# LoRaMicrobit1_0.net
KiCad netlist of a schematic drawn in EAGLE
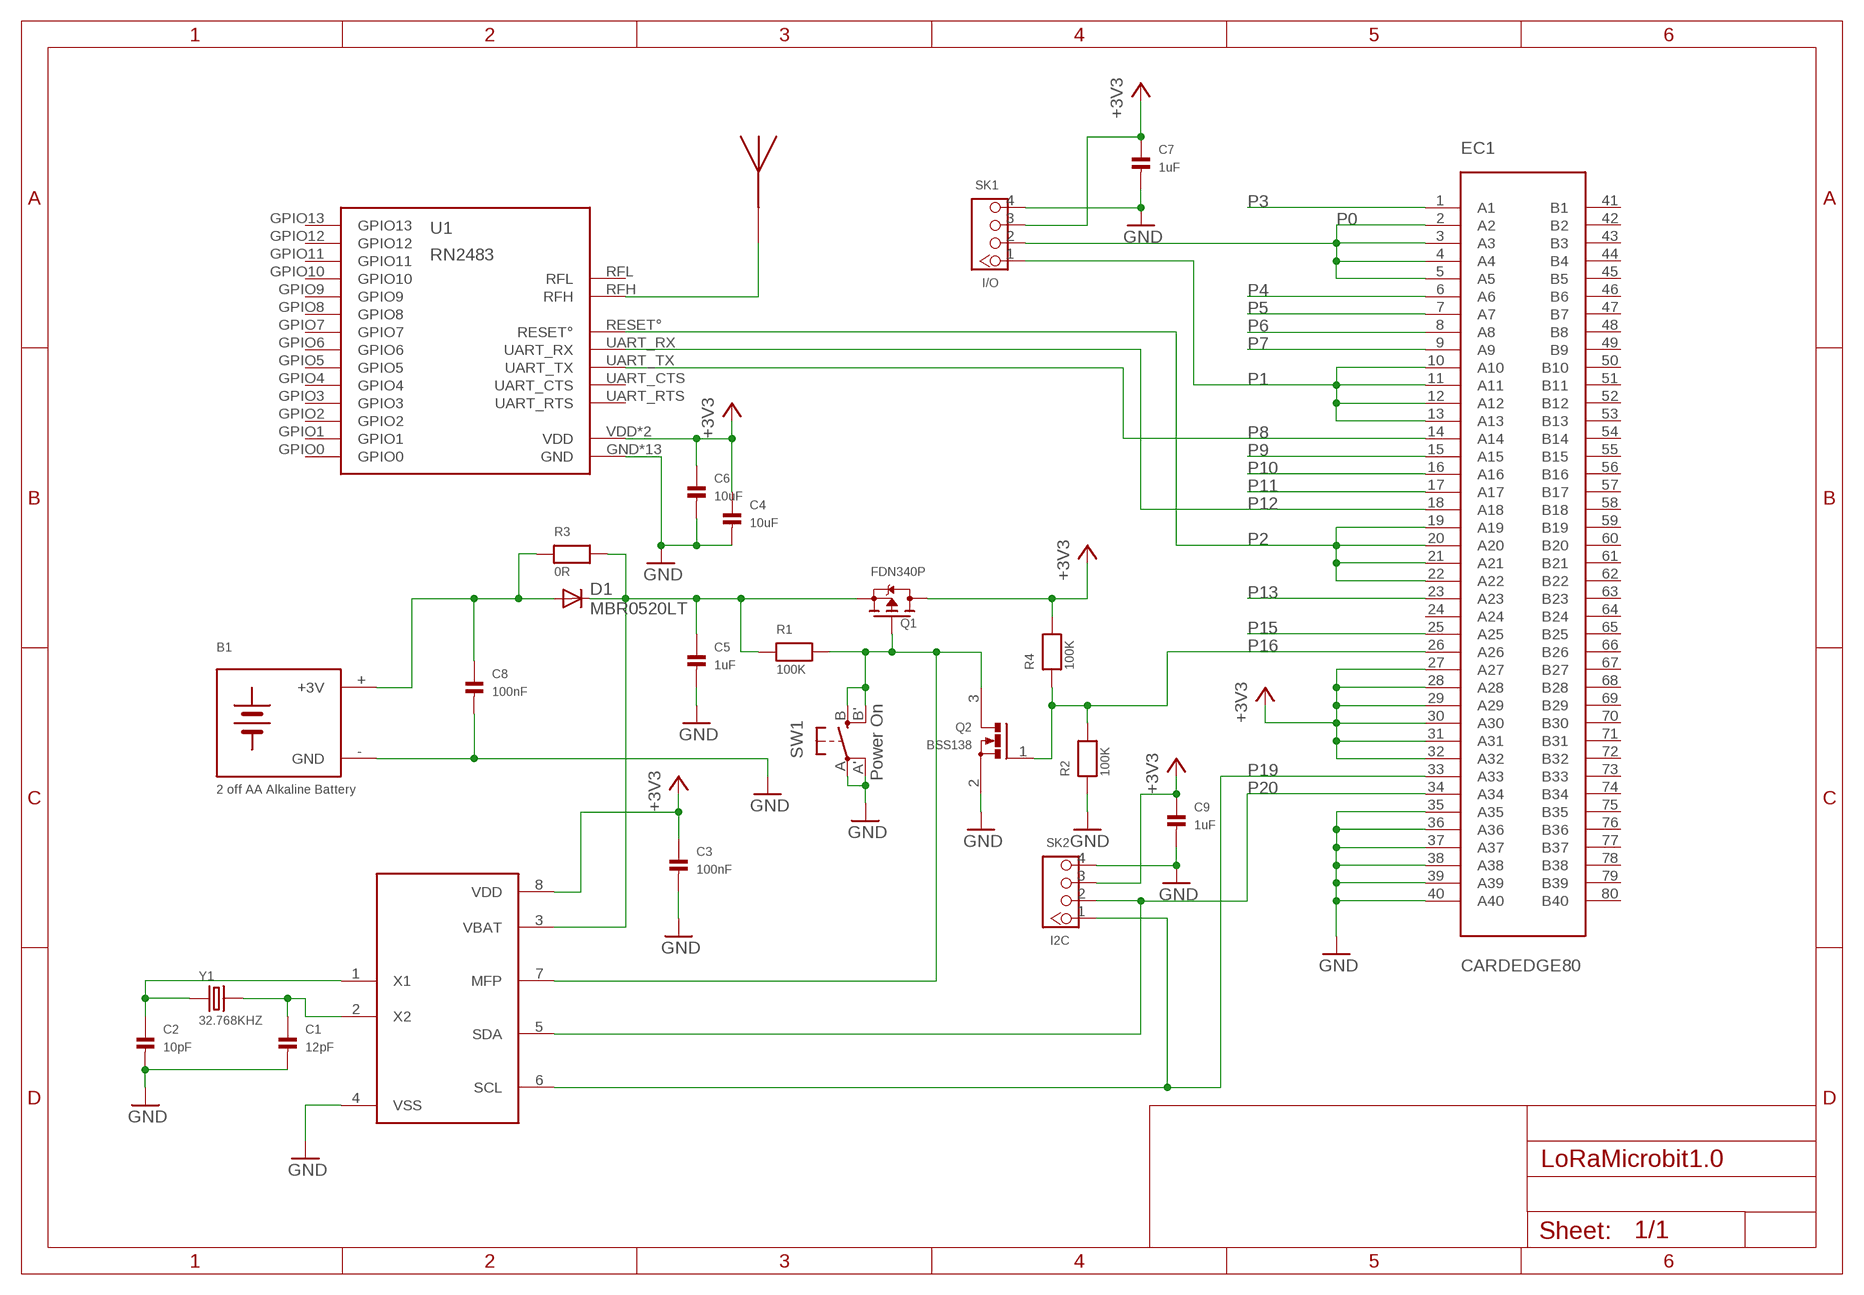
[diagram p0: schematic, sheet 1]

(export (version "E")
  (design (tool "Eeschema 10.0.6"))
  (components
    (comp (ref "B1")
      (value "2 off AA Alkaline Battery")
      (footprint "eagle-import:2AABATTERY")
      (libsource (lib "eagle-import") (part "2AABATTERY"))
    )
    (comp (ref "C1")
      (value "12pF")
      (footprint "eagle-import:0603")
      (libsource (lib "eagle-import") (part "CAP_CERAMIC0603"))
    )
    (comp (ref "C2")
      (value "10pF")
      (footprint "eagle-import:0603")
      (libsource (lib "eagle-import") (part "CAP_CERAMIC0603"))
    )
    (comp (ref "C3")
      (value "100nF")
      (footprint "eagle-import:0603")
      (libsource (lib "eagle-import") (part "CAP_CERAMIC0603"))
    )
    (comp (ref "C4")
      (value "10uF")
      (footprint "eagle-import:0603")
      (libsource (lib "eagle-import") (part "CAP_CERAMIC0603"))
    )
    (comp (ref "C5")
      (value "1uF")
      (footprint "eagle-import:0603")
      (libsource (lib "eagle-import") (part "CAP_CERAMIC0603"))
    )
    (comp (ref "C6")
      (value "10uF")
      (footprint "eagle-import:0603")
      (libsource (lib "eagle-import") (part "CAP_CERAMIC0603"))
    )
    (comp (ref "C7")
      (value "1uF")
      (footprint "eagle-import:0603")
      (libsource (lib "eagle-import") (part "CAP_CERAMIC0603"))
    )
    (comp (ref "C8")
      (value "100nF")
      (footprint "eagle-import:0603")
      (libsource (lib "eagle-import") (part "CAP_CERAMIC0603"))
    )
    (comp (ref "C9")
      (value "1uF")
      (footprint "eagle-import:0603")
      (libsource (lib "eagle-import") (part "CAP_CERAMIC0603"))
    )
    (comp (ref "D1")
      (value "MBR0520LT")
      (footprint "eagle-import:SOD123")
      (libsource (lib "eagle-import") (part "MBR0520LT"))
    )
    (comp (ref "EC1")
      (value "CARDEDGE80")
      (footprint "eagle-import:CARDEDGE80")
      (libsource (lib "eagle-import") (part "CARDEDGE80"))
    )
    (comp (ref "Q1")
      (value "FDN340P")
      (footprint "eagle-import:SOT23-R")
      (libsource (lib "eagle-import") (part "MOSFET-P"))
    )
    (comp (ref "Q2")
      (value "BSS138")
      (footprint "eagle-import:SOT23-R")
      (libsource (lib "eagle-import") (part "MOSFET-NREFLOW"))
    )
    (comp (ref "R1")
      (value "100K")
      (footprint "eagle-import:0603")
      (libsource (lib "eagle-import") (part "RESISTOR0603"))
    )
    (comp (ref "R2")
      (value "100K")
      (footprint "eagle-import:0603")
      (libsource (lib "eagle-import") (part "RESISTOR0603"))
    )
    (comp (ref "R3")
      (value "0R")
      (footprint "eagle-import:0603")
      (libsource (lib "eagle-import") (part "RESISTOR0603"))
    )
    (comp (ref "R4")
      (value "100K")
      (footprint "eagle-import:0603")
      (libsource (lib "eagle-import") (part "RESISTOR0603"))
    )
    (comp (ref "SK1")
      (value "I/O")
      (footprint "eagle-import:HW4-2.0-90D")
      (libsource (lib "eagle-import") (part "GROVE-CONNECTOR-DIP-90D(4P-2.0)"))
    )
    (comp (ref "SK2")
      (value "I2C")
      (footprint "eagle-import:HW4-2.0-90D")
      (libsource (lib "eagle-import") (part "GROVE-CONNECTOR-DIP-90D(4P-2.0)"))
    )
    (comp (ref "SW1")
      (value "Power On")
      (footprint "eagle-import:EVQ-Q2")
      (libsource (lib "eagle-import") (part "SPST_TACT-EVQQ2"))
    )
    (comp (ref "U$2")
      (value "0868AT43A0020")
      (footprint "eagle-import:0868AT043A0020")
      (libsource (lib "eagle-import") (part "0868AT43A0020"))
    )
    (comp (ref "U1")
      (value "RN2483")
      (footprint "eagle-import:RN2483")
      (libsource (lib "eagle-import") (part "RN2483"))
    )
    (comp (ref "U2")
      (value "MCP7940N")
      (footprint "eagle-import:SOIC8-N_MC")
      (libsource (lib "eagle-import") (part "MCP7940N"))
    )
    (comp (ref "Y1")
      (value "32.768KHZ")
      (footprint "eagle-import:X2-SMD-3.2X1.5X0.55MM")
      (fields (field (name "MPN") "FC-135"))
      (libsource (lib "eagle-import") (part "SMD-CRYSTAL-ABS07-32.768KHZ-7PF-20PPM-70K(2P-3.2X1.5MM)"))
    )
  )
  (nets
    (net (code "1") (name "+3V3") (class "Default")
      (node (ref "C3") (pin "1") (pinfunction "P$1_1") (pintype "passive"))
      (node (ref "C4") (pin "1") (pinfunction "P$1_1") (pintype "passive"))
      (node (ref "C6") (pin "1") (pinfunction "P$1_1") (pintype "passive"))
      (node (ref "C7") (pin "1") (pinfunction "P$1_1") (pintype "passive"))
      (node (ref "C9") (pin "1") (pinfunction "P$1_1") (pintype "passive"))
      (node (ref "EC1") (pin "27") (pinfunction "A27_27") (pintype "bidirectional"))
      (node (ref "EC1") (pin "28") (pinfunction "A28_28") (pintype "bidirectional"))
      (node (ref "EC1") (pin "29") (pinfunction "A29_29") (pintype "bidirectional"))
      (node (ref "EC1") (pin "30") (pinfunction "A30_30") (pintype "bidirectional"))
      (node (ref "EC1") (pin "31") (pinfunction "A31_31") (pintype "bidirectional"))
      (node (ref "EC1") (pin "32") (pinfunction "A32_32") (pintype "bidirectional"))
      (node (ref "Q1") (pin "3") (pinfunction "D_3") (pintype "passive"))
      (node (ref "R4") (pin "2") (pinfunction "2_2") (pintype "passive"))
      (node (ref "SK1") (pin "3") (pinfunction "3_3") (pintype "bidirectional"))
      (node (ref "SK2") (pin "3") (pinfunction "3_3") (pintype "bidirectional"))
      (node (ref "U1") (pin "VDD") (pinfunction "VDD_VDD") (pintype "bidirectional"))
      (node (ref "U1") (pin "VDD2") (pinfunction "VDD_VDD2") (pintype "bidirectional"))
      (node (ref "U2") (pin "8") (pinfunction "VDD_8") (pintype "power_in"))
    )
    (net (code "2") (name "/P0") (class "Default")
      (node (ref "EC1") (pin "2") (pinfunction "A2_2") (pintype "bidirectional"))
      (node (ref "EC1") (pin "3") (pinfunction "A3_3") (pintype "bidirectional"))
      (node (ref "EC1") (pin "4") (pinfunction "A4_4") (pintype "bidirectional"))
      (node (ref "EC1") (pin "5") (pinfunction "A5_5") (pintype "bidirectional"))
      (node (ref "SK1") (pin "2") (pinfunction "2_2") (pintype "bidirectional"))
    )
    (net (code "3") (name "/P1") (class "Default")
      (node (ref "EC1") (pin "10") (pinfunction "A10_10") (pintype "bidirectional"))
      (node (ref "EC1") (pin "11") (pinfunction "A11_11") (pintype "bidirectional"))
      (node (ref "EC1") (pin "12") (pinfunction "A12_12") (pintype "bidirectional"))
      (node (ref "EC1") (pin "13") (pinfunction "A13_13") (pintype "bidirectional"))
      (node (ref "SK1") (pin "1") (pinfunction "1_1") (pintype "bidirectional"))
    )
    (net (code "4") (name "/P2") (class "Default")
      (node (ref "EC1") (pin "19") (pinfunction "A19_19") (pintype "bidirectional"))
      (node (ref "EC1") (pin "20") (pinfunction "A20_20") (pintype "bidirectional"))
      (node (ref "EC1") (pin "21") (pinfunction "A21_21") (pintype "bidirectional"))
      (node (ref "EC1") (pin "22") (pinfunction "A22_22") (pintype "bidirectional"))
      (node (ref "U1") (pin "RESET°") (pinfunction "RESET°_RESET°") (pintype "bidirectional"))
    )
    (net (code "5") (name "/P3") (class "Default")
      (node (ref "EC1") (pin "1") (pinfunction "A1_1") (pintype "bidirectional"))
    )
    (net (code "6") (name "/P4") (class "Default")
      (node (ref "EC1") (pin "6") (pinfunction "A6_6") (pintype "bidirectional"))
    )
    (net (code "7") (name "/P5") (class "Default")
      (node (ref "EC1") (pin "7") (pinfunction "A7_7") (pintype "bidirectional"))
    )
    (net (code "8") (name "/P6") (class "Default")
      (node (ref "EC1") (pin "8") (pinfunction "A8_8") (pintype "bidirectional"))
    )
    (net (code "9") (name "/P7") (class "Default")
      (node (ref "EC1") (pin "9") (pinfunction "A9_9") (pintype "bidirectional"))
    )
    (net (code "10") (name "/P8") (class "Default")
      (node (ref "EC1") (pin "14") (pinfunction "A14_14") (pintype "bidirectional"))
      (node (ref "U1") (pin "UART_TX") (pinfunction "UART_TX_UART_TX") (pintype "bidirectional"))
    )
    (net (code "11") (name "/P9") (class "Default")
      (node (ref "EC1") (pin "15") (pinfunction "A15_15") (pintype "bidirectional"))
    )
    (net (code "12") (name "/P10") (class "Default")
      (node (ref "EC1") (pin "16") (pinfunction "A16_16") (pintype "bidirectional"))
    )
    (net (code "13") (name "/P11") (class "Default")
      (node (ref "EC1") (pin "17") (pinfunction "A17_17") (pintype "bidirectional"))
    )
    (net (code "14") (name "/P12") (class "Default")
      (node (ref "EC1") (pin "18") (pinfunction "A18_18") (pintype "bidirectional"))
      (node (ref "U1") (pin "UART_RX") (pinfunction "UART_RX_UART_RX") (pintype "bidirectional"))
    )
    (net (code "15") (name "/P13") (class "Default")
      (node (ref "EC1") (pin "23") (pinfunction "A23_23") (pintype "bidirectional"))
    )
    (net (code "16") (name "/P15") (class "Default")
      (node (ref "EC1") (pin "25") (pinfunction "A25_25") (pintype "bidirectional"))
    )
    (net (code "17") (name "/P16") (class "Default")
      (node (ref "EC1") (pin "26") (pinfunction "A26_26") (pintype "bidirectional"))
      (node (ref "Q2") (pin "1") (pinfunction "G_1") (pintype "bidirectional"))
      (node (ref "R2") (pin "2") (pinfunction "2_2") (pintype "passive"))
      (node (ref "R4") (pin "1") (pinfunction "1_1") (pintype "passive"))
    )
    (net (code "18") (name "/P19") (class "Default")
      (node (ref "EC1") (pin "33") (pinfunction "A33_33") (pintype "bidirectional"))
      (node (ref "SK2") (pin "1") (pinfunction "1_1") (pintype "bidirectional"))
      (node (ref "U2") (pin "6") (pinfunction "SCL_6") (pintype "bidirectional"))
    )
    (net (code "19") (name "/P20") (class "Default")
      (node (ref "EC1") (pin "34") (pinfunction "A34_34") (pintype "bidirectional"))
      (node (ref "SK2") (pin "2") (pinfunction "2_2") (pintype "bidirectional"))
      (node (ref "U2") (pin "5") (pinfunction "SDA_5") (pintype "bidirectional"))
    )
    (net (code "20") (name "GND") (class "Default")
      (node (ref "B1") (pin "-") (pinfunction "GND_-") (pintype "power_in"))
      (node (ref "C1") (pin "2") (pinfunction "P$2_2") (pintype "passive"))
      (node (ref "C2") (pin "2") (pinfunction "P$2_2") (pintype "passive"))
      (node (ref "C3") (pin "2") (pinfunction "P$2_2") (pintype "passive"))
      (node (ref "C4") (pin "2") (pinfunction "P$2_2") (pintype "passive"))
      (node (ref "C5") (pin "2") (pinfunction "P$2_2") (pintype "passive"))
      (node (ref "C6") (pin "2") (pinfunction "P$2_2") (pintype "passive"))
      (node (ref "C7") (pin "2") (pinfunction "P$2_2") (pintype "passive"))
      (node (ref "C8") (pin "2") (pinfunction "P$2_2") (pintype "passive"))
      (node (ref "C9") (pin "2") (pinfunction "P$2_2") (pintype "passive"))
      (node (ref "EC1") (pin "35") (pinfunction "A35_35") (pintype "bidirectional"))
      (node (ref "EC1") (pin "36") (pinfunction "A36_36") (pintype "bidirectional"))
      (node (ref "EC1") (pin "37") (pinfunction "A37_37") (pintype "bidirectional"))
      (node (ref "EC1") (pin "38") (pinfunction "A38_38") (pintype "bidirectional"))
      (node (ref "EC1") (pin "39") (pinfunction "A39_39") (pintype "bidirectional"))
      (node (ref "EC1") (pin "40") (pinfunction "A40_40") (pintype "bidirectional"))
      (node (ref "Q2") (pin "2") (pinfunction "S_2") (pintype "bidirectional"))
      (node (ref "R2") (pin "1") (pinfunction "1_1") (pintype "passive"))
      (node (ref "SK1") (pin "4") (pinfunction "4_4") (pintype "bidirectional"))
      (node (ref "SK2") (pin "4") (pinfunction "4_4") (pintype "bidirectional"))
      (node (ref "SW1") (pin "A") (pinfunction "P_A") (pintype "passive"))
      (node (ref "SW1") (pin "A'") (pinfunction "P1_A'") (pintype "passive"))
      (node (ref "U1") (pin "GND") (pinfunction "GND_GND") (pintype "bidirectional"))
      (node (ref "U1") (pin "GND1") (pinfunction "GND_GND1") (pintype "bidirectional"))
      (node (ref "U1") (pin "GND10") (pinfunction "GND_GND10") (pintype "bidirectional"))
      (node (ref "U1") (pin "GND11") (pinfunction "GND_GND11") (pintype "bidirectional"))
      (node (ref "U1") (pin "GND12") (pinfunction "GND_GND12") (pintype "bidirectional"))
      (node (ref "U1") (pin "GND2") (pinfunction "GND_GND2") (pintype "bidirectional"))
      (node (ref "U1") (pin "GND3") (pinfunction "GND_GND3") (pintype "bidirectional"))
      (node (ref "U1") (pin "GND4") (pinfunction "GND_GND4") (pintype "bidirectional"))
      (node (ref "U1") (pin "GND5") (pinfunction "GND_GND5") (pintype "bidirectional"))
      (node (ref "U1") (pin "GND6") (pinfunction "GND_GND6") (pintype "bidirectional"))
      (node (ref "U1") (pin "GND7") (pinfunction "GND_GND7") (pintype "bidirectional"))
      (node (ref "U1") (pin "GND8") (pinfunction "GND_GND8") (pintype "bidirectional"))
      (node (ref "U1") (pin "GND9") (pinfunction "GND_GND9") (pintype "bidirectional"))
      (node (ref "U2") (pin "4") (pinfunction "VSS_4") (pintype "power_in"))
    )
    (net (code "21") (name "Net-(B1-+3V)") (class "Default")
      (node (ref "B1") (pin "+") (pinfunction "+3V_+") (pintype "power_in"))
      (node (ref "C8") (pin "1") (pinfunction "P$1_1") (pintype "passive"))
      (node (ref "D1") (pin "A") (pinfunction "A_A") (pintype "passive"))
      (node (ref "R3") (pin "1") (pinfunction "1_1") (pintype "passive"))
    )
    (net (code "22") (name "Net-(C1-P$1)") (class "Default")
      (node (ref "C1") (pin "1") (pinfunction "P$1_1") (pintype "passive"))
      (node (ref "U2") (pin "2") (pinfunction "X2_2") (pintype "bidirectional"))
      (node (ref "Y1") (pin "2") (pinfunction "2_2") (pintype "passive"))
    )
    (net (code "23") (name "Net-(C2-P$1)") (class "Default")
      (node (ref "C2") (pin "1") (pinfunction "P$1_1") (pintype "passive"))
      (node (ref "U2") (pin "1") (pinfunction "X1_1") (pintype "bidirectional"))
      (node (ref "Y1") (pin "1") (pinfunction "1_1") (pintype "passive"))
    )
    (net (code "24") (name "Net-(C5-P$1)") (class "Default")
      (node (ref "C5") (pin "1") (pinfunction "P$1_1") (pintype "passive"))
      (node (ref "D1") (pin "C") (pinfunction "C_C") (pintype "passive"))
      (node (ref "Q1") (pin "2") (pinfunction "S_2") (pintype "passive"))
      (node (ref "R1") (pin "1") (pinfunction "1_1") (pintype "passive"))
      (node (ref "R3") (pin "2") (pinfunction "2_2") (pintype "passive"))
      (node (ref "U2") (pin "3") (pinfunction "VBAT_3") (pintype "power_in"))
    )
    (net (code "25") (name "Net-(Q1-G)") (class "Default")
      (node (ref "Q1") (pin "1") (pinfunction "G_1") (pintype "passive"))
      (node (ref "Q2") (pin "3") (pinfunction "D_3") (pintype "bidirectional"))
      (node (ref "R1") (pin "2") (pinfunction "2_2") (pintype "passive"))
      (node (ref "SW1") (pin "B") (pinfunction "S_B") (pintype "passive"))
      (node (ref "SW1") (pin "B'") (pinfunction "S1_B'") (pintype "passive"))
      (node (ref "U2") (pin "7") (pinfunction "MFP_7") (pintype "output"))
    )
    (net (code "26") (name "Net-(U$2-PadP$1)") (class "Default")
      (node (ref "U$2") (pin "P$1") (pinfunction "P$1_P$1") (pintype "bidirectional"))
      (node (ref "U1") (pin "RFH") (pinfunction "RFH_RFH") (pintype "bidirectional"))
    )
    (net (code "27") (name "unconnected-(EC1-A24-Pad24)") (class "Default")
      (node (ref "EC1") (pin "24") (pinfunction "A24_24") (pintype "bidirectional"))
    )
    (net (code "28") (name "unconnected-(EC1-B1-Pad41)") (class "Default")
      (node (ref "EC1") (pin "41") (pinfunction "B1_41") (pintype "bidirectional"))
    )
    (net (code "29") (name "unconnected-(EC1-B2-Pad42)") (class "Default")
      (node (ref "EC1") (pin "42") (pinfunction "B2_42") (pintype "bidirectional"))
    )
    (net (code "30") (name "unconnected-(EC1-B3-Pad43)") (class "Default")
      (node (ref "EC1") (pin "43") (pinfunction "B3_43") (pintype "bidirectional"))
    )
    (net (code "31") (name "unconnected-(EC1-B4-Pad44)") (class "Default")
      (node (ref "EC1") (pin "44") (pinfunction "B4_44") (pintype "bidirectional"))
    )
    (net (code "32") (name "unconnected-(EC1-B5-Pad45)") (class "Default")
      (node (ref "EC1") (pin "45") (pinfunction "B5_45") (pintype "bidirectional"))
    )
    (net (code "33") (name "unconnected-(EC1-B6-Pad46)") (class "Default")
      (node (ref "EC1") (pin "46") (pinfunction "B6_46") (pintype "bidirectional"))
    )
    (net (code "34") (name "unconnected-(EC1-B7-Pad47)") (class "Default")
      (node (ref "EC1") (pin "47") (pinfunction "B7_47") (pintype "bidirectional"))
    )
    (net (code "35") (name "unconnected-(EC1-B8-Pad48)") (class "Default")
      (node (ref "EC1") (pin "48") (pinfunction "B8_48") (pintype "bidirectional"))
    )
    (net (code "36") (name "unconnected-(EC1-B9-Pad49)") (class "Default")
      (node (ref "EC1") (pin "49") (pinfunction "B9_49") (pintype "bidirectional"))
    )
    (net (code "37") (name "unconnected-(EC1-B10-Pad50)") (class "Default")
      (node (ref "EC1") (pin "50") (pinfunction "B10_50") (pintype "bidirectional"))
    )
    (net (code "38") (name "unconnected-(EC1-B11-Pad51)") (class "Default")
      (node (ref "EC1") (pin "51") (pinfunction "B11_51") (pintype "bidirectional"))
    )
    (net (code "39") (name "unconnected-(EC1-B12-Pad52)") (class "Default")
      (node (ref "EC1") (pin "52") (pinfunction "B12_52") (pintype "bidirectional"))
    )
    (net (code "40") (name "unconnected-(EC1-B13-Pad53)") (class "Default")
      (node (ref "EC1") (pin "53") (pinfunction "B13_53") (pintype "bidirectional"))
    )
    (net (code "41") (name "unconnected-(EC1-B14-Pad54)") (class "Default")
      (node (ref "EC1") (pin "54") (pinfunction "B14_54") (pintype "bidirectional"))
    )
    (net (code "42") (name "unconnected-(EC1-B15-Pad55)") (class "Default")
      (node (ref "EC1") (pin "55") (pinfunction "B15_55") (pintype "bidirectional"))
    )
    (net (code "43") (name "unconnected-(EC1-B16-Pad56)") (class "Default")
      (node (ref "EC1") (pin "56") (pinfunction "B16_56") (pintype "bidirectional"))
    )
    (net (code "44") (name "unconnected-(EC1-B17-Pad57)") (class "Default")
      (node (ref "EC1") (pin "57") (pinfunction "B17_57") (pintype "bidirectional"))
    )
    (net (code "45") (name "unconnected-(EC1-B18-Pad58)") (class "Default")
      (node (ref "EC1") (pin "58") (pinfunction "B18_58") (pintype "bidirectional"))
    )
    (net (code "46") (name "unconnected-(EC1-B19-Pad59)") (class "Default")
      (node (ref "EC1") (pin "59") (pinfunction "B19_59") (pintype "bidirectional"))
    )
    (net (code "47") (name "unconnected-(EC1-B20-Pad60)") (class "Default")
      (node (ref "EC1") (pin "60") (pinfunction "B20_60") (pintype "bidirectional"))
    )
    (net (code "48") (name "unconnected-(EC1-B21-Pad61)") (class "Default")
      (node (ref "EC1") (pin "61") (pinfunction "B21_61") (pintype "bidirectional"))
    )
    (net (code "49") (name "unconnected-(EC1-B22-Pad62)") (class "Default")
      (node (ref "EC1") (pin "62") (pinfunction "B22_62") (pintype "bidirectional"))
    )
    (net (code "50") (name "unconnected-(EC1-B23-Pad63)") (class "Default")
      (node (ref "EC1") (pin "63") (pinfunction "B23_63") (pintype "bidirectional"))
    )
    (net (code "51") (name "unconnected-(EC1-B24-Pad64)") (class "Default")
      (node (ref "EC1") (pin "64") (pinfunction "B24_64") (pintype "bidirectional"))
    )
    (net (code "52") (name "unconnected-(EC1-B25-Pad65)") (class "Default")
      (node (ref "EC1") (pin "65") (pinfunction "B25_65") (pintype "bidirectional"))
    )
    (net (code "53") (name "unconnected-(EC1-B26-Pad66)") (class "Default")
      (node (ref "EC1") (pin "66") (pinfunction "B26_66") (pintype "bidirectional"))
    )
    (net (code "54") (name "unconnected-(EC1-B27-Pad67)") (class "Default")
      (node (ref "EC1") (pin "67") (pinfunction "B27_67") (pintype "bidirectional"))
    )
    (net (code "55") (name "unconnected-(EC1-B28-Pad68)") (class "Default")
      (node (ref "EC1") (pin "68") (pinfunction "B28_68") (pintype "bidirectional"))
    )
    (net (code "56") (name "unconnected-(EC1-B29-Pad69)") (class "Default")
      (node (ref "EC1") (pin "69") (pinfunction "B29_69") (pintype "bidirectional"))
    )
    (net (code "57") (name "unconnected-(EC1-B30-Pad70)") (class "Default")
      (node (ref "EC1") (pin "70") (pinfunction "B30_70") (pintype "bidirectional"))
    )
    (net (code "58") (name "unconnected-(EC1-B31-Pad71)") (class "Default")
      (node (ref "EC1") (pin "71") (pinfunction "B31_71") (pintype "bidirectional"))
    )
    (net (code "59") (name "unconnected-(EC1-B32-Pad72)") (class "Default")
      (node (ref "EC1") (pin "72") (pinfunction "B32_72") (pintype "bidirectional"))
    )
    (net (code "60") (name "unconnected-(EC1-B33-Pad73)") (class "Default")
      (node (ref "EC1") (pin "73") (pinfunction "B33_73") (pintype "bidirectional"))
    )
    (net (code "61") (name "unconnected-(EC1-B34-Pad74)") (class "Default")
      (node (ref "EC1") (pin "74") (pinfunction "B34_74") (pintype "bidirectional"))
    )
    (net (code "62") (name "unconnected-(EC1-B35-Pad75)") (class "Default")
      (node (ref "EC1") (pin "75") (pinfunction "B35_75") (pintype "bidirectional"))
    )
    (net (code "63") (name "unconnected-(EC1-B36-Pad76)") (class "Default")
      (node (ref "EC1") (pin "76") (pinfunction "B36_76") (pintype "bidirectional"))
    )
    (net (code "64") (name "unconnected-(EC1-B37-Pad77)") (class "Default")
      (node (ref "EC1") (pin "77") (pinfunction "B37_77") (pintype "bidirectional"))
    )
    (net (code "65") (name "unconnected-(EC1-B38-Pad78)") (class "Default")
      (node (ref "EC1") (pin "78") (pinfunction "B38_78") (pintype "bidirectional"))
    )
    (net (code "66") (name "unconnected-(EC1-B39-Pad79)") (class "Default")
      (node (ref "EC1") (pin "79") (pinfunction "B39_79") (pintype "bidirectional"))
    )
    (net (code "67") (name "unconnected-(EC1-B40-Pad80)") (class "Default")
      (node (ref "EC1") (pin "80") (pinfunction "B40_80") (pintype "bidirectional"))
    )
    (net (code "68") (name "unconnected-(U1-PadGPIO0)") (class "Default")
      (node (ref "U1") (pin "GPIO0") (pinfunction "GPIO0_GPIO0") (pintype "bidirectional"))
    )
    (net (code "69") (name "unconnected-(U1-PadGPIO1)") (class "Default")
      (node (ref "U1") (pin "GPIO1") (pinfunction "GPIO1_GPIO1") (pintype "bidirectional"))
    )
    (net (code "70") (name "unconnected-(U1-PadGPIO2)") (class "Default")
      (node (ref "U1") (pin "GPIO2") (pinfunction "GPIO2_GPIO2") (pintype "bidirectional"))
    )
    (net (code "71") (name "unconnected-(U1-PadGPIO3)") (class "Default")
      (node (ref "U1") (pin "GPIO3") (pinfunction "GPIO3_GPIO3") (pintype "bidirectional"))
    )
    (net (code "72") (name "unconnected-(U1-PadGPIO4)") (class "Default")
      (node (ref "U1") (pin "GPIO4") (pinfunction "GPIO4_GPIO4") (pintype "bidirectional"))
    )
    (net (code "73") (name "unconnected-(U1-PadGPIO5)") (class "Default")
      (node (ref "U1") (pin "GPIO5") (pinfunction "GPIO5_GPIO5") (pintype "bidirectional"))
    )
    (net (code "74") (name "unconnected-(U1-PadGPIO6)") (class "Default")
      (node (ref "U1") (pin "GPIO6") (pinfunction "GPIO6_GPIO6") (pintype "bidirectional"))
    )
    (net (code "75") (name "unconnected-(U1-PadGPIO7)") (class "Default")
      (node (ref "U1") (pin "GPIO7") (pinfunction "GPIO7_GPIO7") (pintype "bidirectional"))
    )
    (net (code "76") (name "unconnected-(U1-PadGPIO8)") (class "Default")
      (node (ref "U1") (pin "GPIO8") (pinfunction "GPIO8_GPIO8") (pintype "bidirectional"))
    )
    (net (code "77") (name "unconnected-(U1-PadGPIO9)") (class "Default")
      (node (ref "U1") (pin "GPIO9") (pinfunction "GPIO9_GPIO9") (pintype "bidirectional"))
    )
    (net (code "78") (name "unconnected-(U1-PadGPIO10)") (class "Default")
      (node (ref "U1") (pin "GPIO10") (pinfunction "GPIO10_GPIO10") (pintype "bidirectional"))
    )
    (net (code "79") (name "unconnected-(U1-PadGPIO11)") (class "Default")
      (node (ref "U1") (pin "GPIO11") (pinfunction "GPIO11_GPIO11") (pintype "bidirectional"))
    )
    (net (code "80") (name "unconnected-(U1-PadGPIO12)") (class "Default")
      (node (ref "U1") (pin "GPIO12") (pinfunction "GPIO12_GPIO12") (pintype "bidirectional"))
    )
    (net (code "81") (name "unconnected-(U1-PadGPIO13)") (class "Default")
      (node (ref "U1") (pin "GPIO13") (pinfunction "GPIO13_GPIO13") (pintype "bidirectional"))
    )
    (net (code "82") (name "unconnected-(U1-PadRFL)") (class "Default")
      (node (ref "U1") (pin "RFL") (pinfunction "RFL_RFL") (pintype "bidirectional"))
    )
    (net (code "83") (name "unconnected-(U1-PadUART_CTS)") (class "Default")
      (node (ref "U1") (pin "UART_CTS") (pinfunction "UART_CTS_UART_CTS") (pintype "bidirectional"))
    )
    (net (code "84") (name "unconnected-(U1-PadUART_RTS)") (class "Default")
      (node (ref "U1") (pin "UART_RTS") (pinfunction "UART_RTS_UART_RTS") (pintype "bidirectional"))
    )
  )
)
